# Audio.net
KiCad netlist of a schematic drawn in Altium Designer
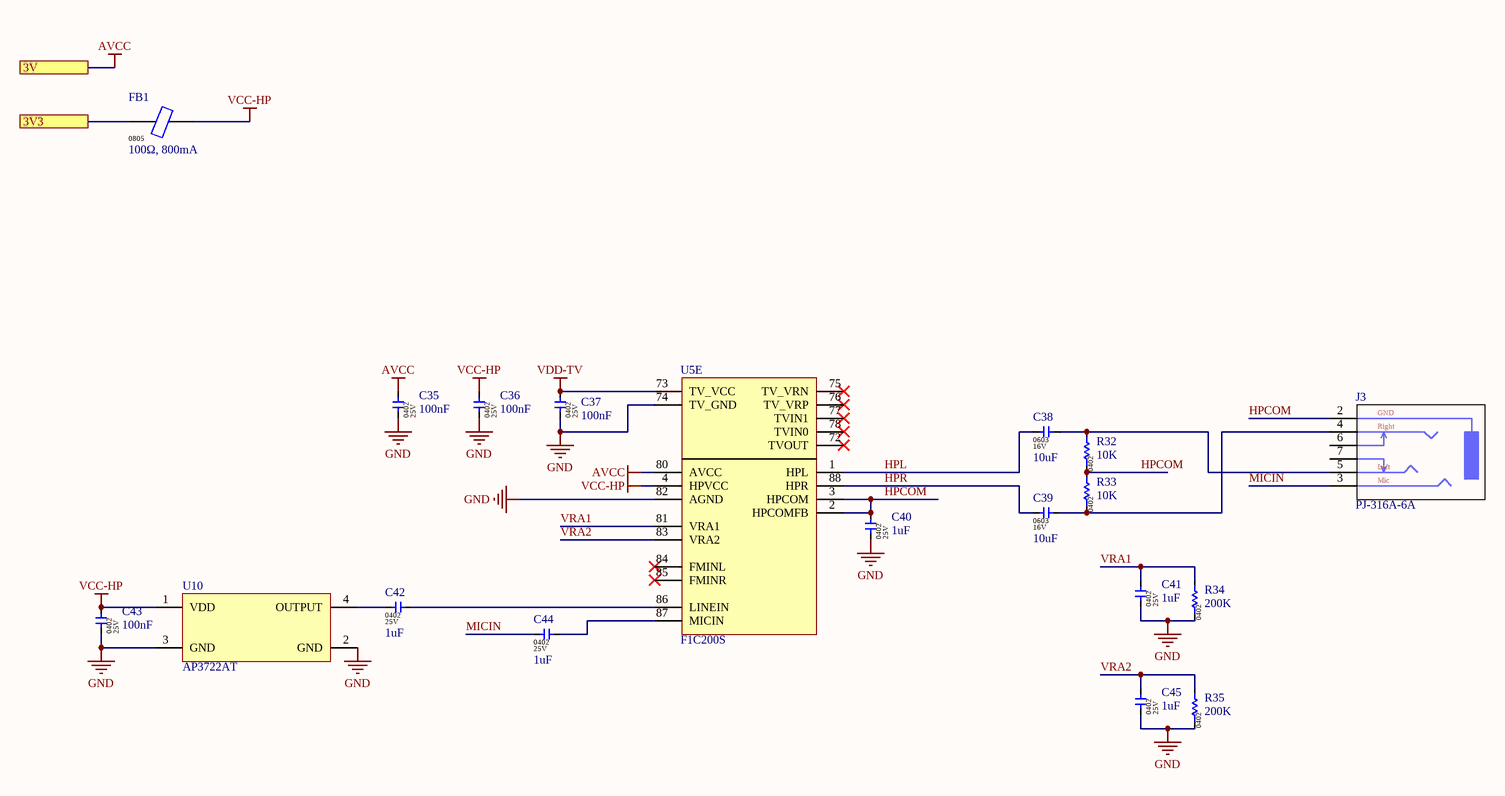
[diagram p0: Audio.SchDoc]

(export (version "E")
  (design (tool "Eeschema 10.0.6"))
  (components
    (comp (ref "C35")
      (value "100nF")
      (footprint "CAP-0402")
      (description "100nF ±10% 25V X5R 0402 Multilayer Ceramic Capacitors MLCC - SMD/SMT RoHS")
      (fields (field (name "MANUFACTURE PART") "0402X104K250CT") (field (name "VOLTAGE") "25V"))
      (libsource (lib "Capacitor Database") (part "Cap-non-polarized"))
    )
    (comp (ref "C36")
      (value "100nF")
      (footprint "CAP-0402")
      (description "100nF ±10% 25V X5R 0402 Multilayer Ceramic Capacitors MLCC - SMD/SMT RoHS")
      (fields (field (name "MANUFACTURE PART") "0402X104K250CT") (field (name "VOLTAGE") "25V"))
      (libsource (lib "Capacitor Database") (part "Cap-non-polarized"))
    )
    (comp (ref "C37")
      (value "100nF")
      (footprint "CAP-0402")
      (description "100nF ±10% 25V X5R 0402 Multilayer Ceramic Capacitors MLCC - SMD/SMT RoHS")
      (fields (field (name "MANUFACTURE PART") "0402X104K250CT") (field (name "VOLTAGE") "25V"))
      (libsource (lib "Capacitor Database") (part "Cap-non-polarized"))
    )
    (comp (ref "C38")
      (value "10uF")
      (footprint "CAP-0603")
      (description "16V 10uF X5R ±20% 0603 Multilayer Ceramic Capacitors MLCC - SMD/SMT ROHS")
      (fields (field (name "MANUFACTURE PART") "0603X106M160CT") (field (name "VOLTAGE") "16V"))
      (libsource (lib "Capacitor Database") (part "Cap-non-polarized"))
    )
    (comp (ref "C39")
      (value "10uF")
      (footprint "CAP-0603")
      (description "16V 10uF X5R ±20% 0603 Multilayer Ceramic Capacitors MLCC - SMD/SMT ROHS")
      (fields (field (name "MANUFACTURE PART") "0603X106M160CT") (field (name "VOLTAGE") "16V"))
      (libsource (lib "Capacitor Database") (part "Cap-non-polarized"))
    )
    (comp (ref "C40")
      (value "1uF")
      (footprint "CAP-0402")
      (description "25V 1uF X5R ±10% 0402 Multilayer Ceramic Capacitors MLCC - SMD/SMT ROHS")
      (fields (field (name "MANUFACTURE PART") "0402X105K250CT") (field (name "VOLTAGE") "25V"))
      (libsource (lib "Capacitor Database") (part "Cap-non-polarized"))
    )
    (comp (ref "C41")
      (value "1uF")
      (footprint "CAP-0402")
      (description "25V 1uF X5R ±10% 0402 Multilayer Ceramic Capacitors MLCC - SMD/SMT ROHS")
      (fields (field (name "MANUFACTURE PART") "0402X105K250CT") (field (name "VOLTAGE") "25V"))
      (libsource (lib "Capacitor Database") (part "Cap-non-polarized"))
    )
    (comp (ref "C42")
      (value "1uF")
      (footprint "CAP-0402")
      (description "25V 1uF X5R ±10% 0402 Multilayer Ceramic Capacitors MLCC - SMD/SMT ROHS")
      (fields (field (name "MANUFACTURE PART") "0402X105K250CT") (field (name "VOLTAGE") "25V"))
      (libsource (lib "Capacitor Database") (part "Cap-non-polarized"))
    )
    (comp (ref "C43")
      (value "100nF")
      (footprint "CAP-0402")
      (description "100nF ±10% 25V X5R 0402 Multilayer Ceramic Capacitors MLCC - SMD/SMT RoHS")
      (fields (field (name "MANUFACTURE PART") "0402X104K250CT") (field (name "VOLTAGE") "25V"))
      (libsource (lib "Capacitor Database") (part "Cap-non-polarized"))
    )
    (comp (ref "C44")
      (value "1uF")
      (footprint "CAP-0402")
      (description "25V 1uF X5R ±10% 0402 Multilayer Ceramic Capacitors MLCC - SMD/SMT ROHS")
      (fields (field (name "MANUFACTURE PART") "0402X105K250CT") (field (name "VOLTAGE") "25V"))
      (libsource (lib "Capacitor Database") (part "Cap-non-polarized"))
    )
    (comp (ref "C45")
      (value "1uF")
      (footprint "CAP-0402")
      (description "25V 1uF X5R ±10% 0402 Multilayer Ceramic Capacitors MLCC - SMD/SMT ROHS")
      (fields (field (name "MANUFACTURE PART") "0402X105K250CT") (field (name "VOLTAGE") "25V"))
      (libsource (lib "Capacitor Database") (part "Cap-non-polarized"))
    )
    (comp (ref "FB1")
      (value "100Ω, 800mA")
      (footprint "Ferrite-0805")
      (description "100Ω @ 100MHz 800mA 1 150mΩ 0805 Ferrite Beads RoHS")
      (fields (field (name "MANUFACTURE PART") "GZ2012D101TF"))
      (libsource (lib "Filter Database") (part "Ferrite Beads"))
    )
    (comp (ref "J3")
      (value "PJ-316A-6A")
      (footprint "Audio 3.5mm, 6 pin")
      (description "3.5mm SMD Headphone Holder 6 Female Horizontal SMD Audio & Video Connectors RoHS")
      (libsource (lib "Connectors, Misc") (part "Audio 3.5 - 6 pin"))
    )
    (comp (ref "R32")
      (value "10K")
      (footprint "RES-0402")
      (description "10kΩ ±1% 1/16W ±100ppm/℃ 0402 Chip Resistor - Surface Mount RoHS")
      (fields (field (name "MANUFACTURE PART") "WR04X1002FTL"))
      (libsource (lib "Resistor Database") (part "Resistor"))
    )
    (comp (ref "R33")
      (value "10K")
      (footprint "RES-0402")
      (description "10kΩ ±1% 1/16W ±100ppm/℃ 0402 Chip Resistor - Surface Mount RoHS")
      (fields (field (name "MANUFACTURE PART") "WR04X1002FTL"))
      (libsource (lib "Resistor Database") (part "Resistor"))
    )
    (comp (ref "R34")
      (value "200K")
      (footprint "RES-0402")
      (description "200kΩ ±1% 1/16W ±100ppm/℃ 0402 Chip Resistor - Surface Mount RoHS")
      (fields (field (name "MANUFACTURE PART") "WR04X2003FTL"))
      (libsource (lib "Resistor Database") (part "Resistor"))
    )
    (comp (ref "R35")
      (value "200K")
      (footprint "RES-0402")
      (description "200kΩ ±1% 1/16W ±100ppm/℃ 0402 Chip Resistor - Surface Mount RoHS")
      (fields (field (name "MANUFACTURE PART") "WR04X2003FTL"))
      (libsource (lib "Resistor Database") (part "Resistor"))
    )
    (comp (ref "U5")
      (value "F1C200S")
      (footprint "F1Cx00s")
      (description "The Allwinner F1C200s is a small SoC with an ARM926EJ-S CPU core and 64MB of embedded DDR SDRAM.")
      (libsource (lib "IC Database") (part "F1CX00S"))
    )
    (comp (ref "U10")
      (value "AP3722AT")
      (footprint "AP3722AT")
      (description "SMD,3.76x2.24x1.1mm MEMS Microphones ROHS")
      (libsource (lib "IC Database") (part "AP3722AT"))
    )
  )
  (nets
    (net (code "1") (name "/3V3") (class "Default") (node (ref "FB1") (pin "1") (pintype "passive")))
    (net (code "2") (name "/HPCOM") (class "Default")
      (node (ref "C40") (pin "2") (pinfunction "2_2") (pintype "passive"))
      (node (ref "J3") (pin "2") (pintype "passive"))
      (node (ref "R32") (pin "1") (pinfunction "1_1") (pintype "passive"))
      (node (ref "R33") (pin "2") (pinfunction "2_2") (pintype "passive"))
      (node (ref "U5") (pin "2") (pinfunction "HPCOMFB_2") (pintype "passive"))
      (node (ref "U5") (pin "3") (pinfunction "HPCOM_3") (pintype "passive"))
    )
    (net (code "3") (name "/HPL") (class "Default")
      (node (ref "C38") (pin "1") (pinfunction "1_1") (pintype "passive"))
      (node (ref "U5") (pin "1") (pinfunction "HPL_1") (pintype "passive"))
    )
    (net (code "4") (name "/HPR") (class "Default")
      (node (ref "C39") (pin "1") (pinfunction "1_1") (pintype "passive"))
      (node (ref "U5") (pin "88") (pinfunction "HPR_88") (pintype "passive"))
    )
    (net (code "5") (name "/MICIN") (class "Default")
      (node (ref "C44") (pin "1") (pinfunction "1_1") (pintype "passive"))
      (node (ref "J3") (pin "3") (pintype "passive"))
    )
    (net (code "6") (name "/VRA1") (class "Default")
      (node (ref "C41") (pin "2") (pinfunction "2_2") (pintype "passive"))
      (node (ref "R34") (pin "2") (pinfunction "2_2") (pintype "passive"))
      (node (ref "U5") (pin "81") (pinfunction "VRA1_81") (pintype "passive"))
    )
    (net (code "7") (name "/VRA2") (class "Default")
      (node (ref "C45") (pin "2") (pinfunction "2_2") (pintype "passive"))
      (node (ref "R35") (pin "2") (pinfunction "2_2") (pintype "passive"))
      (node (ref "U5") (pin "83") (pinfunction "VRA2_83") (pintype "passive"))
    )
    (net (code "8") (name "AVCC") (class "Default")
      (node (ref "C35") (pin "2") (pinfunction "2_2") (pintype "passive"))
      (node (ref "U5") (pin "80") (pinfunction "AVCC_80") (pintype "passive"))
    )
    (net (code "9") (name "GND") (class "Default")
      (node (ref "C35") (pin "1") (pinfunction "1_1") (pintype "passive"))
      (node (ref "C36") (pin "1") (pinfunction "1_1") (pintype "passive"))
      (node (ref "C37") (pin "1") (pinfunction "1_1") (pintype "passive"))
      (node (ref "C40") (pin "1") (pinfunction "1_1") (pintype "passive"))
      (node (ref "C41") (pin "1") (pinfunction "1_1") (pintype "passive"))
      (node (ref "C43") (pin "1") (pinfunction "1_1") (pintype "passive"))
      (node (ref "C45") (pin "1") (pinfunction "1_1") (pintype "passive"))
      (node (ref "R34") (pin "1") (pinfunction "1_1") (pintype "passive"))
      (node (ref "R35") (pin "1") (pinfunction "1_1") (pintype "passive"))
      (node (ref "U10") (pin "2") (pinfunction "GND_2") (pintype "power_in"))
      (node (ref "U10") (pin "3") (pinfunction "GND_3") (pintype "passive"))
      (node (ref "U5") (pin "74") (pinfunction "TV_GND_74") (pintype "passive"))
      (node (ref "U5") (pin "82") (pinfunction "AGND_82") (pintype "passive"))
    )
    (net (code "10") (name "Net-(C38-Pad2)") (class "Default")
      (node (ref "C38") (pin "2") (pinfunction "2_2") (pintype "passive"))
      (node (ref "J3") (pin "5") (pintype "passive"))
      (node (ref "R32") (pin "2") (pinfunction "2_2") (pintype "passive"))
    )
    (net (code "11") (name "Net-(C39-Pad2)") (class "Default")
      (node (ref "C39") (pin "2") (pinfunction "2_2") (pintype "passive"))
      (node (ref "J3") (pin "4") (pintype "passive"))
      (node (ref "R33") (pin "1") (pinfunction "1_1") (pintype "passive"))
    )
    (net (code "12") (name "Net-(U5E-LINEIN)") (class "Default")
      (node (ref "C42") (pin "2") (pinfunction "2_2") (pintype "passive"))
      (node (ref "U5") (pin "86") (pinfunction "LINEIN_86") (pintype "passive"))
    )
    (net (code "13") (name "Net-(U5E-MICIN)") (class "Default")
      (node (ref "C44") (pin "2") (pinfunction "2_2") (pintype "passive"))
      (node (ref "U5") (pin "87") (pinfunction "MICIN_87") (pintype "passive"))
    )
    (net (code "14") (name "Net-(U10-OUTPUT)") (class "Default")
      (node (ref "C42") (pin "1") (pinfunction "1_1") (pintype "passive"))
      (node (ref "U10") (pin "4") (pinfunction "OUTPUT_4") (pintype "passive"))
    )
    (net (code "15") (name "VCC-HP") (class "Default")
      (node (ref "C36") (pin "2") (pinfunction "2_2") (pintype "passive"))
      (node (ref "C43") (pin "2") (pinfunction "2_2") (pintype "passive"))
      (node (ref "FB1") (pin "2") (pintype "passive"))
      (node (ref "U10") (pin "1") (pinfunction "VDD_1") (pintype "power_in"))
      (node (ref "U5") (pin "4") (pinfunction "HPVCC_4") (pintype "passive"))
    )
    (net (code "16") (name "VDD-TV") (class "Default")
      (node (ref "C37") (pin "2") (pinfunction "2_2") (pintype "passive"))
      (node (ref "U5") (pin "73") (pinfunction "TV_VCC_73") (pintype "passive"))
    )
    (net (code "17") (name "unconnected-(J3-Pad6)") (class "Default")
      (node (ref "J3") (pin "6") (pintype "passive"))
    )
    (net (code "18") (name "unconnected-(J3-Pad7)") (class "Default")
      (node (ref "J3") (pin "7") (pintype "passive"))
    )
    (net (code "19") (name "unconnected-(U5E-FMINL-Pad84)") (class "Default")
      (node (ref "U5") (pin "84") (pinfunction "FMINL_84") (pintype "passive+no_connect"))
    )
    (net (code "20") (name "unconnected-(U5E-FMINR-Pad85)") (class "Default")
      (node (ref "U5") (pin "85") (pinfunction "FMINR_85") (pintype "passive+no_connect"))
    )
    (net (code "21") (name "unconnected-(U5E-TVIN0-Pad78)") (class "Default")
      (node (ref "U5") (pin "78") (pinfunction "TVIN0_78") (pintype "passive+no_connect"))
    )
    (net (code "22") (name "unconnected-(U5E-TVIN1-Pad77)") (class "Default")
      (node (ref "U5") (pin "77") (pinfunction "TVIN1_77") (pintype "passive+no_connect"))
    )
    (net (code "23") (name "unconnected-(U5E-TVOUT-Pad72)") (class "Default")
      (node (ref "U5") (pin "72") (pinfunction "TVOUT_72") (pintype "passive+no_connect"))
    )
    (net (code "24") (name "unconnected-(U5E-TV_VRN-Pad75)") (class "Default")
      (node (ref "U5") (pin "75") (pinfunction "TV_VRN_75") (pintype "passive+no_connect"))
    )
    (net (code "25") (name "unconnected-(U5E-TV_VRP-Pad76)") (class "Default")
      (node (ref "U5") (pin "76") (pinfunction "TV_VRP_76") (pintype "passive+no_connect"))
    )
  )
)
